# Atmega_328P.net
KiCad netlist of a schematic drawn in EAGLE
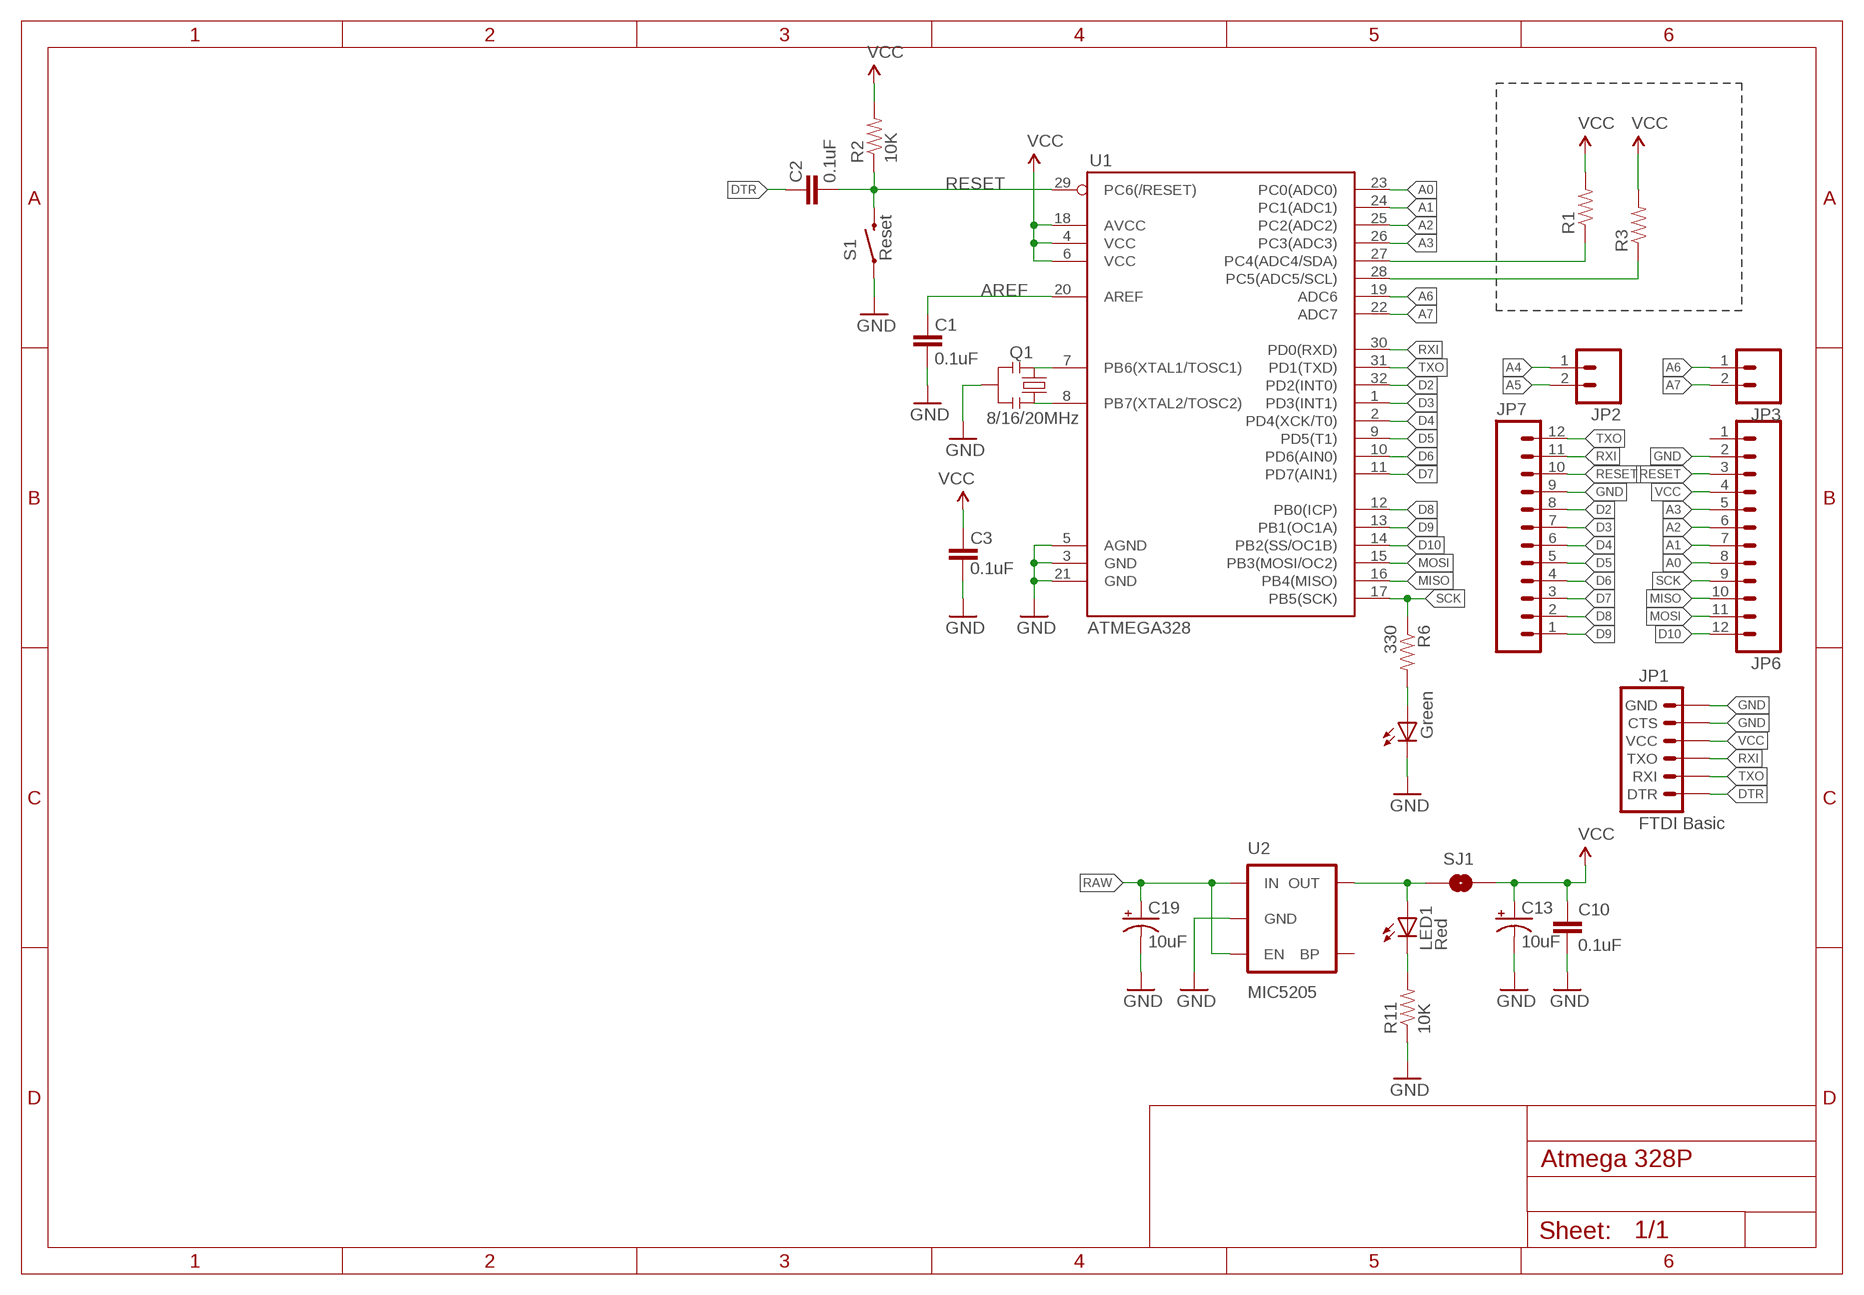
[diagram p0: schematic, sheet 1]

(export (version "E")
  (design (tool "Eeschema 10.0.6"))
  (components
    (comp (ref "C1")
      (value "0.1uF")
      (footprint "eagle-import:0603-CAP")
      (libsource (lib "eagle-import") (part "CAP0603-CAP"))
    )
    (comp (ref "C2")
      (value "0.1uF")
      (footprint "eagle-import:0603-CAP")
      (libsource (lib "eagle-import") (part "CAP0603-CAP"))
    )
    (comp (ref "C3")
      (value "0.1uF")
      (footprint "eagle-import:0603-CAP")
      (libsource (lib "eagle-import") (part "CAP0603-CAP"))
    )
    (comp (ref "C10")
      (value "0.1uF")
      (footprint "eagle-import:0603-CAP")
      (libsource (lib "eagle-import") (part "CAP0603-CAP"))
    )
    (comp (ref "C13")
      (value "10uF")
      (footprint "eagle-import:EIA3216")
      (libsource (lib "eagle-import") (part "CAP_POL1206"))
    )
    (comp (ref "C19")
      (value "10uF")
      (footprint "eagle-import:EIA3216")
      (libsource (lib "eagle-import") (part "CAP_POL1206"))
    )
    (comp (ref "D3")
      (value "Green")
      (footprint "eagle-import:0603-LED-ALT1")
      (libsource (lib "eagle-import") (part "LED"))
    )
    (comp (ref "JP1")
      (value "FTDI Basic")
      (footprint "eagle-import:1X06")
      (libsource (lib "eagle-import") (part "ARDUINO_SERIAL_PROGRAMPTH"))
    )
    (comp (ref "JP2")
      (value "M02PTH")
      (footprint "eagle-import:1X02")
      (libsource (lib "eagle-import") (part "M02PTH"))
    )
    (comp (ref "JP3")
      (value "M02PTH")
      (footprint "eagle-import:1X02")
      (libsource (lib "eagle-import") (part "M02PTH"))
    )
    (comp (ref "JP6")
      (value "M12PTH")
      (footprint "eagle-import:1X12")
      (libsource (lib "eagle-import") (part "M12PTH"))
    )
    (comp (ref "JP7")
      (value "M12PTH")
      (footprint "eagle-import:1X12")
      (libsource (lib "eagle-import") (part "M12PTH"))
    )
    (comp (ref "LED1")
      (value "Red")
      (footprint "eagle-import:0603-LED-ALT1")
      (libsource (lib "eagle-import") (part "LED"))
    )
    (comp (ref "Q1")
      (value "8/16/20MHz")
      (footprint "eagle-import:RESONATOR-SMD-1_1")
      (libsource (lib "eagle-import") (part "RESONATOR1{colon}1"))
    )
    (comp (ref "R1")
      (value "RESISTOR0603-RES")
      (footprint "eagle-import:0603-RES")
      (libsource (lib "eagle-import") (part "RESISTOR0603-RES"))
    )
    (comp (ref "R2")
      (value "10K")
      (footprint "eagle-import:0603-RES")
      (libsource (lib "eagle-import") (part "RESISTOR0603-RES"))
    )
    (comp (ref "R3")
      (value "RESISTOR0603-RES")
      (footprint "eagle-import:0603-RES")
      (libsource (lib "eagle-import") (part "RESISTOR0603-RES"))
    )
    (comp (ref "R6")
      (value "330")
      (footprint "eagle-import:0603-RES")
      (libsource (lib "eagle-import") (part "RESISTOR0603-RES"))
    )
    (comp (ref "R11")
      (value "10K")
      (footprint "eagle-import:0603-RES")
      (libsource (lib "eagle-import") (part "RESISTOR0603-RES"))
    )
    (comp (ref "S1")
      (value "Reset")
      (footprint "eagle-import:TACTILE-SWITCH-SMD-ALT01")
      (libsource (lib "eagle-import") (part "SWITCH-MOMENTARY-2SMD-ALT01"))
    )
    (comp (ref "SJ1")
      (value "SOLDERJUMPERNC")
      (footprint "eagle-import:SJ_2S")
      (libsource (lib "eagle-import") (part "SOLDERJUMPERNC"))
    )
    (comp (ref "U1")
      (value "ATMEGA328")
      (footprint "eagle-import:TQFP32-08")
      (libsource (lib "eagle-import") (part "ATMEGA168"))
    )
    (comp (ref "U2")
      (value "MIC5205")
      (footprint "eagle-import:SOT23-5")
      (libsource (lib "eagle-import") (part "V_REG_LDOSMD"))
    )
  )
  (nets
    (net (code "1") (name "/AREF") (class "Default")
      (node (ref "C1") (pin "2") (pinfunction "2_2") (pintype "passive"))
      (node (ref "U1") (pin "20") (pinfunction "AREF_20") (pintype "bidirectional"))
    )
    (net (code "2") (name "A0") (class "Default")
      (node (ref "JP6") (pin "8") (pinfunction "8_8") (pintype "passive"))
      (node (ref "U1") (pin "23") (pinfunction "PC0(ADC0)_23") (pintype "bidirectional"))
    )
    (net (code "3") (name "A1") (class "Default")
      (node (ref "JP6") (pin "7") (pinfunction "7_7") (pintype "passive"))
      (node (ref "U1") (pin "24") (pinfunction "PC1(ADC1)_24") (pintype "bidirectional"))
    )
    (net (code "4") (name "A2") (class "Default")
      (node (ref "JP6") (pin "6") (pinfunction "6_6") (pintype "passive"))
      (node (ref "U1") (pin "25") (pinfunction "PC2(ADC2)_25") (pintype "bidirectional"))
    )
    (net (code "5") (name "A3") (class "Default")
      (node (ref "JP6") (pin "5") (pinfunction "5_5") (pintype "passive"))
      (node (ref "U1") (pin "26") (pinfunction "PC3(ADC3)_26") (pintype "bidirectional"))
    )
    (net (code "6") (name "A4") (class "Default")
      (node (ref "JP2") (pin "1") (pinfunction "1_1") (pintype "passive"))
      (node (ref "R1") (pin "1") (pinfunction "1_1") (pintype "passive"))
      (node (ref "U1") (pin "27") (pinfunction "PC4(ADC4/SDA)_27") (pintype "bidirectional"))
    )
    (net (code "7") (name "A5") (class "Default")
      (node (ref "JP2") (pin "2") (pinfunction "2_2") (pintype "passive"))
      (node (ref "R3") (pin "1") (pinfunction "1_1") (pintype "passive"))
      (node (ref "U1") (pin "28") (pinfunction "PC5(ADC5/SCL)_28") (pintype "bidirectional"))
    )
    (net (code "8") (name "A6") (class "Default")
      (node (ref "JP3") (pin "1") (pinfunction "1_1") (pintype "passive"))
      (node (ref "U1") (pin "19") (pinfunction "ADC6_19") (pintype "bidirectional"))
    )
    (net (code "9") (name "A7") (class "Default")
      (node (ref "JP3") (pin "2") (pinfunction "2_2") (pintype "passive"))
      (node (ref "U1") (pin "22") (pinfunction "ADC7_22") (pintype "bidirectional"))
    )
    (net (code "10") (name "D2") (class "Default")
      (node (ref "JP7") (pin "8") (pinfunction "8_8") (pintype "passive"))
      (node (ref "U1") (pin "32") (pinfunction "PD2(INT0)_32") (pintype "bidirectional"))
    )
    (net (code "11") (name "D3") (class "Default")
      (node (ref "JP7") (pin "7") (pinfunction "7_7") (pintype "passive"))
      (node (ref "U1") (pin "1") (pinfunction "PD3(INT1)_1") (pintype "bidirectional"))
    )
    (net (code "12") (name "D4") (class "Default")
      (node (ref "JP7") (pin "6") (pinfunction "6_6") (pintype "passive"))
      (node (ref "U1") (pin "2") (pinfunction "PD4(XCK/T0)_2") (pintype "bidirectional"))
    )
    (net (code "13") (name "D5") (class "Default")
      (node (ref "JP7") (pin "5") (pinfunction "5_5") (pintype "passive"))
      (node (ref "U1") (pin "9") (pinfunction "PD5(T1)_9") (pintype "bidirectional"))
    )
    (net (code "14") (name "D6") (class "Default")
      (node (ref "JP7") (pin "4") (pinfunction "4_4") (pintype "passive"))
      (node (ref "U1") (pin "10") (pinfunction "PD6(AIN0)_10") (pintype "bidirectional"))
    )
    (net (code "15") (name "D7") (class "Default")
      (node (ref "JP7") (pin "3") (pinfunction "3_3") (pintype "passive"))
      (node (ref "U1") (pin "11") (pinfunction "PD7(AIN1)_11") (pintype "bidirectional"))
    )
    (net (code "16") (name "D8") (class "Default")
      (node (ref "JP7") (pin "2") (pinfunction "2_2") (pintype "passive"))
      (node (ref "U1") (pin "12") (pinfunction "PB0(ICP)_12") (pintype "bidirectional"))
    )
    (net (code "17") (name "D9") (class "Default")
      (node (ref "JP7") (pin "1") (pinfunction "1_1") (pintype "passive"))
      (node (ref "U1") (pin "13") (pinfunction "PB1(OC1A)_13") (pintype "bidirectional"))
    )
    (net (code "18") (name "D10") (class "Default")
      (node (ref "JP6") (pin "12") (pinfunction "12_12") (pintype "passive"))
      (node (ref "U1") (pin "14") (pinfunction "PB2(SS/OC1B)_14") (pintype "bidirectional"))
    )
    (net (code "19") (name "DTR") (class "Default")
      (node (ref "C2") (pin "2") (pinfunction "2_2") (pintype "passive"))
      (node (ref "JP1") (pin "1") (pinfunction "DTR_1") (pintype "passive"))
    )
    (net (code "20") (name "GND") (class "Default")
      (node (ref "C1") (pin "1") (pinfunction "1_1") (pintype "passive"))
      (node (ref "C10") (pin "2") (pinfunction "2_2") (pintype "passive"))
      (node (ref "C13") (pin "C") (pinfunction "-_C") (pintype "passive"))
      (node (ref "C19") (pin "C") (pinfunction "-_C") (pintype "passive"))
      (node (ref "C3") (pin "1") (pinfunction "1_1") (pintype "passive"))
      (node (ref "D3") (pin "C") (pinfunction "C_C") (pintype "passive"))
      (node (ref "JP1") (pin "5") (pinfunction "CTS_5") (pintype "passive"))
      (node (ref "JP1") (pin "6") (pinfunction "GND_6") (pintype "passive"))
      (node (ref "JP6") (pin "2") (pinfunction "2_2") (pintype "passive"))
      (node (ref "JP7") (pin "9") (pinfunction "9_9") (pintype "passive"))
      (node (ref "Q1") (pin "2") (pinfunction "2_2") (pintype "passive"))
      (node (ref "R11") (pin "1") (pinfunction "1_1") (pintype "passive"))
      (node (ref "S1") (pin "1") (pinfunction "1_1") (pintype "passive"))
      (node (ref "S1") (pin "2") (pinfunction "1_2") (pintype "passive"))
      (node (ref "U1") (pin "21") (pinfunction "GND_21") (pintype "bidirectional"))
      (node (ref "U1") (pin "3") (pinfunction "GND_3") (pintype "bidirectional"))
      (node (ref "U1") (pin "5") (pinfunction "AGND_5") (pintype "bidirectional"))
      (node (ref "U2") (pin "2") (pinfunction "GND_2") (pintype "input"))
    )
    (net (code "21") (name "MISO") (class "Default")
      (node (ref "JP6") (pin "10") (pinfunction "10_10") (pintype "passive"))
      (node (ref "U1") (pin "16") (pinfunction "PB4(MISO)_16") (pintype "bidirectional"))
    )
    (net (code "22") (name "MOSI") (class "Default")
      (node (ref "JP6") (pin "11") (pinfunction "11_11") (pintype "passive"))
      (node (ref "U1") (pin "15") (pinfunction "PB3(MOSI/OC2)_15") (pintype "bidirectional"))
    )
    (net (code "23") (name "Net-(D3-PadA)") (class "Default")
      (node (ref "D3") (pin "A") (pinfunction "A_A") (pintype "passive"))
      (node (ref "R6") (pin "2") (pinfunction "2_2") (pintype "passive"))
    )
    (net (code "24") (name "Net-(LED1-PadC)") (class "Default")
      (node (ref "LED1") (pin "C") (pinfunction "C_C") (pintype "passive"))
      (node (ref "R11") (pin "2") (pinfunction "2_2") (pintype "passive"))
    )
    (net (code "25") (name "Net-(U1-PB6(XTAL1{slash}TOSC1))") (class "Default")
      (node (ref "Q1") (pin "1") (pinfunction "1_1") (pintype "passive"))
      (node (ref "U1") (pin "7") (pinfunction "PB6(XTAL1/TOSC1)_7") (pintype "bidirectional"))
    )
    (net (code "26") (name "Net-(U1-PB7(XTAL2{slash}TOSC2))") (class "Default")
      (node (ref "Q1") (pin "3") (pinfunction "3_3") (pintype "passive"))
      (node (ref "U1") (pin "8") (pinfunction "PB7(XTAL2/TOSC2)_8") (pintype "bidirectional"))
    )
    (net (code "27") (name "Net-(U2-OUT)") (class "Default")
      (node (ref "LED1") (pin "A") (pinfunction "A_A") (pintype "passive"))
      (node (ref "SJ1") (pin "1") (pinfunction "1_1") (pintype "passive"))
      (node (ref "U2") (pin "5") (pinfunction "OUT_5") (pintype "passive"))
    )
    (net (code "28") (name "RAW") (class "Default")
      (node (ref "C19") (pin "A") (pinfunction "+_A") (pintype "passive"))
      (node (ref "U2") (pin "1") (pinfunction "IN_1") (pintype "input"))
      (node (ref "U2") (pin "3") (pinfunction "EN_3") (pintype "input"))
    )
    (net (code "29") (name "RESET") (class "Default")
      (node (ref "C2") (pin "1") (pinfunction "1_1") (pintype "passive"))
      (node (ref "JP6") (pin "3") (pinfunction "3_3") (pintype "passive"))
      (node (ref "JP7") (pin "10") (pinfunction "10_10") (pintype "passive"))
      (node (ref "R2") (pin "1") (pinfunction "1_1") (pintype "passive"))
      (node (ref "S1") (pin "3") (pinfunction "2_3") (pintype "passive"))
      (node (ref "S1") (pin "4") (pinfunction "2_4") (pintype "passive"))
      (node (ref "U1") (pin "29") (pinfunction "PC6(/RESET)_29") (pintype "bidirectional"))
    )
    (net (code "30") (name "RXI") (class "Default")
      (node (ref "JP1") (pin "3") (pinfunction "TXO_3") (pintype "passive"))
      (node (ref "JP7") (pin "11") (pinfunction "11_11") (pintype "passive"))
      (node (ref "U1") (pin "30") (pinfunction "PD0(RXD)_30") (pintype "bidirectional"))
    )
    (net (code "31") (name "SCK") (class "Default")
      (node (ref "JP6") (pin "9") (pinfunction "9_9") (pintype "passive"))
      (node (ref "R6") (pin "1") (pinfunction "1_1") (pintype "passive"))
      (node (ref "U1") (pin "17") (pinfunction "PB5(SCK)_17") (pintype "bidirectional"))
    )
    (net (code "32") (name "TXO") (class "Default")
      (node (ref "JP1") (pin "2") (pinfunction "RXI_2") (pintype "passive"))
      (node (ref "JP7") (pin "12") (pinfunction "12_12") (pintype "passive"))
      (node (ref "U1") (pin "31") (pinfunction "PD1(TXD)_31") (pintype "bidirectional"))
    )
    (net (code "33") (name "VCC") (class "Default")
      (node (ref "C10") (pin "1") (pinfunction "1_1") (pintype "passive"))
      (node (ref "C13") (pin "A") (pinfunction "+_A") (pintype "passive"))
      (node (ref "C3") (pin "2") (pinfunction "2_2") (pintype "passive"))
      (node (ref "JP1") (pin "4") (pinfunction "VCC_4") (pintype "passive"))
      (node (ref "JP6") (pin "4") (pinfunction "4_4") (pintype "passive"))
      (node (ref "R1") (pin "2") (pinfunction "2_2") (pintype "passive"))
      (node (ref "R2") (pin "2") (pinfunction "2_2") (pintype "passive"))
      (node (ref "R3") (pin "2") (pinfunction "2_2") (pintype "passive"))
      (node (ref "SJ1") (pin "2") (pinfunction "2_2") (pintype "passive"))
      (node (ref "U1") (pin "18") (pinfunction "AVCC_18") (pintype "bidirectional"))
      (node (ref "U1") (pin "4") (pinfunction "VCC_4") (pintype "bidirectional"))
      (node (ref "U1") (pin "6") (pinfunction "VCC_6") (pintype "bidirectional"))
    )
    (net (code "34") (name "unconnected-(JP6-Pad1)") (class "Default")
      (node (ref "JP6") (pin "1") (pinfunction "1_1") (pintype "passive"))
    )
    (net (code "35") (name "unconnected-(U2-BP-Pad4)") (class "Default")
      (node (ref "U2") (pin "4") (pinfunction "BP_4") (pintype "input"))
    )
  )
)
